# unodongdiendienap.net
KiCad netlist of a schematic drawn in Altium Designer
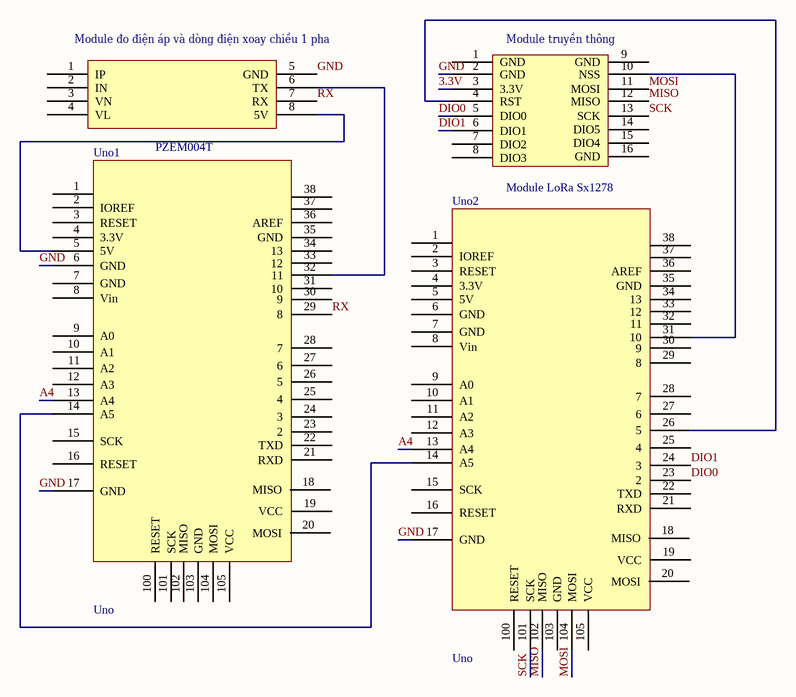
[diagram p0: unodongdiendienap.SchDoc]

(export (version "E")
  (design (tool "Eeschema 10.0.6"))
  (components
    (comp (ref "Module truyền thông")
      (value "Module LoRa Sx1278")
      (footprint "PCBLoRa")
      (libsource (lib "LoRa") (part "Component_1"))
    )
    (comp (ref "Module đo điện áp và dòng điện xoay chiều 1 pha")
      (value "PZEM004T")
      (libsource (lib "pzem") (part "PZEM004T"))
    )
    (comp (ref "Uno1") (value "Uno") (footprint "PCBComponent_1") (libsource (lib "uno") (part "Uno")))
    (comp (ref "Uno2") (value "Uno") (footprint "PCBComponent_1") (libsource (lib "uno") (part "Uno")))
  )
  (nets
    (net (code "1") (name "/3.3V") (class "Default")
      (node (ref "Module truyền thông") (pin "3") (pinfunction "3.3V_3") (pintype "passive"))
    )
    (net (code "2") (name "/A4") (class "Default")
      (node (ref "Uno1") (pin "13") (pinfunction "A4_13") (pintype "passive"))
      (node (ref "Uno2") (pin "13") (pinfunction "A4_13") (pintype "passive"))
    )
    (net (code "3") (name "/DIO0") (class "Default")
      (node (ref "Module truyền thông") (pin "5") (pinfunction "DIO0_5") (pintype "passive"))
      (node (ref "Uno2") (pin "23") (pinfunction "2_23") (pintype "passive"))
    )
    (net (code "4") (name "/DIO1") (class "Default")
      (node (ref "Module truyền thông") (pin "6") (pinfunction "DIO1_6") (pintype "passive"))
      (node (ref "Uno2") (pin "24") (pinfunction "3_24") (pintype "passive"))
    )
    (net (code "5") (name "/GND") (class "Default")
      (node (ref "Module truyền thông") (pin "2") (pinfunction "GND_2") (pintype "passive"))
      (node (ref "Module đo điện áp và dòng điện xoay chiều 1 pha") (pin "5") (pinfunction "GND_5") (pintype "passive"))
      (node (ref "Uno1") (pin "17") (pinfunction "GND_17") (pintype "passive"))
      (node (ref "Uno1") (pin "6") (pinfunction "GND_6") (pintype "passive"))
      (node (ref "Uno2") (pin "17") (pinfunction "GND_17") (pintype "passive"))
    )
    (net (code "6") (name "/MISO") (class "Default")
      (node (ref "Module truyền thông") (pin "12") (pinfunction "MISO_12") (pintype "passive"))
      (node (ref "Uno2") (pin "102") (pinfunction "MISO_102") (pintype "passive"))
    )
    (net (code "7") (name "/MOSI") (class "Default")
      (node (ref "Module truyền thông") (pin "11") (pinfunction "MOSI_11") (pintype "passive"))
      (node (ref "Uno2") (pin "104") (pinfunction "MOSI_104") (pintype "passive"))
    )
    (net (code "8") (name "/RX") (class "Default")
      (node (ref "Module đo điện áp và dòng điện xoay chiều 1 pha") (pin "7") (pinfunction "RX_7") (pintype "passive"))
      (node (ref "Uno1") (pin "29") (pinfunction "8_29") (pintype "passive"))
    )
    (net (code "9") (name "/SCK") (class "Default")
      (node (ref "Module truyền thông") (pin "13") (pinfunction "SCK_13") (pintype "passive"))
      (node (ref "Uno2") (pin "101") (pinfunction "SCK_101") (pintype "passive"))
    )
    (net (code "10") (name "Net-(Module truyền thông-NSS)") (class "Default")
      (node (ref "Module truyền thông") (pin "10") (pinfunction "NSS_10") (pintype "passive"))
      (node (ref "Uno2") (pin "31") (pinfunction "10_31") (pintype "passive"))
    )
    (net (code "11") (name "Net-(Module truyền thông-RST)") (class "Default")
      (node (ref "Module truyền thông") (pin "4") (pinfunction "RST_4") (pintype "passive"))
      (node (ref "Uno2") (pin "26") (pinfunction "5_26") (pintype "passive"))
    )
    (net (code "12") (name "Net-(Module đo điện áp và dòng điện xoay chiều 1 pha-5V)") (class "Default")
      (node (ref "Module đo điện áp và dòng điện xoay chiều 1 pha") (pin "8") (pinfunction "5V_8") (pintype "passive"))
      (node (ref "Uno1") (pin "5") (pinfunction "5V_5") (pintype "passive"))
    )
    (net (code "13") (name "Net-(Module đo điện áp và dòng điện xoay chiều 1 pha-TX)") (class "Default")
      (node (ref "Module đo điện áp và dòng điện xoay chiều 1 pha") (pin "6") (pinfunction "TX_6") (pintype "passive"))
      (node (ref "Uno1") (pin "32") (pinfunction "11_32") (pintype "passive"))
    )
    (net (code "14") (name "Net-(Uno1-A5)") (class "Default")
      (node (ref "Uno1") (pin "14") (pinfunction "A5_14") (pintype "passive"))
      (node (ref "Uno2") (pin "14") (pinfunction "A5_14") (pintype "passive"))
    )
    (net (code "15") (name "unconnected-(Module truyền thông-DIO2-Pad7)") (class "Default")
      (node (ref "Module truyền thông") (pin "7") (pinfunction "DIO2_7") (pintype "passive"))
    )
    (net (code "16") (name "unconnected-(Module truyền thông-DIO3-Pad8)") (class "Default")
      (node (ref "Module truyền thông") (pin "8") (pinfunction "DIO3_8") (pintype "passive"))
    )
    (net (code "17") (name "unconnected-(Module truyền thông-DIO4-Pad15)") (class "Default")
      (node (ref "Module truyền thông") (pin "15") (pinfunction "DIO4_15") (pintype "passive"))
    )
    (net (code "18") (name "unconnected-(Module truyền thông-DIO5-Pad14)") (class "Default")
      (node (ref "Module truyền thông") (pin "14") (pinfunction "DIO5_14") (pintype "passive"))
    )
    (net (code "19") (name "unconnected-(Module truyền thông-GND-Pad1)") (class "Default")
      (node (ref "Module truyền thông") (pin "1") (pinfunction "GND_1") (pintype "passive"))
    )
    (net (code "20") (name "unconnected-(Module truyền thông-GND-Pad9)") (class "Default")
      (node (ref "Module truyền thông") (pin "9") (pinfunction "GND_9") (pintype "passive"))
    )
    (net (code "21") (name "unconnected-(Module truyền thông-GND-Pad16)") (class "Default")
      (node (ref "Module truyền thông") (pin "16") (pinfunction "GND_16") (pintype "passive"))
    )
    (net (code "22") (name "unconnected-(Module đo điện áp và dòng điện xoay chiều 1 pha-IN-Pad2)") (class "Default")
      (node (ref "Module đo điện áp và dòng điện xoay chiều 1 pha") (pin "2") (pinfunction "IN_2") (pintype "passive"))
    )
    (net (code "23") (name "unconnected-(Module đo điện áp và dòng điện xoay chiều 1 pha-IP-Pad1)") (class "Default")
      (node (ref "Module đo điện áp và dòng điện xoay chiều 1 pha") (pin "1") (pinfunction "IP_1") (pintype "passive"))
    )
    (net (code "24") (name "unconnected-(Module đo điện áp và dòng điện xoay chiều 1 pha-VL-Pad4)") (class "Default")
      (node (ref "Module đo điện áp và dòng điện xoay chiều 1 pha") (pin "4") (pinfunction "VL_4") (pintype "passive"))
    )
    (net (code "25") (name "unconnected-(Module đo điện áp và dòng điện xoay chiều 1 pha-VN-Pad3)") (class "Default")
      (node (ref "Module đo điện áp và dòng điện xoay chiều 1 pha") (pin "3") (pinfunction "VN_3") (pintype "passive"))
    )
    (net (code "26") (name "unconnected-(Uno1-2-Pad23)") (class "Default")
      (node (ref "Uno1") (pin "23") (pinfunction "2_23") (pintype "passive"))
    )
    (net (code "27") (name "unconnected-(Uno1-3-Pad24)") (class "Default")
      (node (ref "Uno1") (pin "24") (pinfunction "3_24") (pintype "passive"))
    )
    (net (code "28") (name "unconnected-(Uno1-3.3V-Pad4)") (class "Default")
      (node (ref "Uno1") (pin "4") (pinfunction "3.3V_4") (pintype "passive"))
    )
    (net (code "29") (name "unconnected-(Uno1-4-Pad25)") (class "Default")
      (node (ref "Uno1") (pin "25") (pinfunction "4_25") (pintype "passive"))
    )
    (net (code "30") (name "unconnected-(Uno1-5-Pad26)") (class "Default")
      (node (ref "Uno1") (pin "26") (pinfunction "5_26") (pintype "passive"))
    )
    (net (code "31") (name "unconnected-(Uno1-6-Pad27)") (class "Default")
      (node (ref "Uno1") (pin "27") (pinfunction "6_27") (pintype "passive"))
    )
    (net (code "32") (name "unconnected-(Uno1-7-Pad28)") (class "Default")
      (node (ref "Uno1") (pin "28") (pinfunction "7_28") (pintype "passive"))
    )
    (net (code "33") (name "unconnected-(Uno1-9-Pad30)") (class "Default")
      (node (ref "Uno1") (pin "30") (pinfunction "9_30") (pintype "passive"))
    )
    (net (code "34") (name "unconnected-(Uno1-10-Pad31)") (class "Default")
      (node (ref "Uno1") (pin "31") (pinfunction "10_31") (pintype "passive"))
    )
    (net (code "35") (name "unconnected-(Uno1-12-Pad33)") (class "Default")
      (node (ref "Uno1") (pin "33") (pinfunction "12_33") (pintype "passive"))
    )
    (net (code "36") (name "unconnected-(Uno1-13-Pad34)") (class "Default")
      (node (ref "Uno1") (pin "34") (pinfunction "13_34") (pintype "passive"))
    )
    (net (code "37") (name "unconnected-(Uno1-A0-Pad9)") (class "Default")
      (node (ref "Uno1") (pin "9") (pinfunction "A0_9") (pintype "passive"))
    )
    (net (code "38") (name "unconnected-(Uno1-A1-Pad10)") (class "Default")
      (node (ref "Uno1") (pin "10") (pinfunction "A1_10") (pintype "passive"))
    )
    (net (code "39") (name "unconnected-(Uno1-A2-Pad11)") (class "Default")
      (node (ref "Uno1") (pin "11") (pinfunction "A2_11") (pintype "passive"))
    )
    (net (code "40") (name "unconnected-(Uno1-A3-Pad12)") (class "Default")
      (node (ref "Uno1") (pin "12") (pinfunction "A3_12") (pintype "passive"))
    )
    (net (code "41") (name "unconnected-(Uno1-AREF-Pad36)") (class "Default")
      (node (ref "Uno1") (pin "36") (pinfunction "AREF_36") (pintype "passive"))
    )
    (net (code "42") (name "unconnected-(Uno1-GND-Pad7)") (class "Default")
      (node (ref "Uno1") (pin "7") (pinfunction "GND_7") (pintype "passive"))
    )
    (net (code "43") (name "unconnected-(Uno1-GND-Pad35)") (class "Default")
      (node (ref "Uno1") (pin "35") (pinfunction "GND_35") (pintype "passive"))
    )
    (net (code "44") (name "unconnected-(Uno1-GND-Pad103)") (class "Default")
      (node (ref "Uno1") (pin "103") (pinfunction "GND_103") (pintype "passive"))
    )
    (net (code "45") (name "unconnected-(Uno1-IOREF-Pad2)") (class "Default")
      (node (ref "Uno1") (pin "2") (pinfunction "IOREF_2") (pintype "passive"))
    )
    (net (code "46") (name "unconnected-(Uno1-MISO-Pad18)") (class "Default")
      (node (ref "Uno1") (pin "18") (pinfunction "MISO_18") (pintype "passive"))
    )
    (net (code "47") (name "unconnected-(Uno1-MISO-Pad102)") (class "Default")
      (node (ref "Uno1") (pin "102") (pinfunction "MISO_102") (pintype "passive"))
    )
    (net (code "48") (name "unconnected-(Uno1-MOSI-Pad20)") (class "Default")
      (node (ref "Uno1") (pin "20") (pinfunction "MOSI_20") (pintype "passive"))
    )
    (net (code "49") (name "unconnected-(Uno1-MOSI-Pad104)") (class "Default")
      (node (ref "Uno1") (pin "104") (pinfunction "MOSI_104") (pintype "passive"))
    )
    (net (code "50") (name "unconnected-(Uno1-Pad1)") (class "Default")
      (node (ref "Uno1") (pin "1") (pintype "passive"))
    )
    (net (code "51") (name "unconnected-(Uno1-Pad37)") (class "Default")
      (node (ref "Uno1") (pin "37") (pintype "passive"))
    )
    (net (code "52") (name "unconnected-(Uno1-Pad38)") (class "Default")
      (node (ref "Uno1") (pin "38") (pintype "passive"))
    )
    (net (code "53") (name "unconnected-(Uno1-RESET-Pad3)") (class "Default")
      (node (ref "Uno1") (pin "3") (pinfunction "RESET_3") (pintype "passive"))
    )
    (net (code "54") (name "unconnected-(Uno1-RESET-Pad16)") (class "Default")
      (node (ref "Uno1") (pin "16") (pinfunction "RESET_16") (pintype "passive"))
    )
    (net (code "55") (name "unconnected-(Uno1-RESET-Pad100)") (class "Default")
      (node (ref "Uno1") (pin "100") (pinfunction "RESET_100") (pintype "passive"))
    )
    (net (code "56") (name "unconnected-(Uno1-RXD-Pad21)") (class "Default")
      (node (ref "Uno1") (pin "21") (pinfunction "RXD_21") (pintype "passive"))
    )
    (net (code "57") (name "unconnected-(Uno1-SCK-Pad15)") (class "Default")
      (node (ref "Uno1") (pin "15") (pinfunction "SCK_15") (pintype "passive"))
    )
    (net (code "58") (name "unconnected-(Uno1-SCK-Pad101)") (class "Default")
      (node (ref "Uno1") (pin "101") (pinfunction "SCK_101") (pintype "passive"))
    )
    (net (code "59") (name "unconnected-(Uno1-TXD-Pad22)") (class "Default")
      (node (ref "Uno1") (pin "22") (pinfunction "TXD_22") (pintype "passive"))
    )
    (net (code "60") (name "unconnected-(Uno1-VCC-Pad19)") (class "Default")
      (node (ref "Uno1") (pin "19") (pinfunction "VCC_19") (pintype "passive"))
    )
    (net (code "61") (name "unconnected-(Uno1-VCC-Pad105)") (class "Default")
      (node (ref "Uno1") (pin "105") (pinfunction "VCC_105") (pintype "passive"))
    )
    (net (code "62") (name "unconnected-(Uno1-Vin-Pad8)") (class "Default")
      (node (ref "Uno1") (pin "8") (pinfunction "Vin_8") (pintype "passive"))
    )
    (net (code "63") (name "unconnected-(Uno2-3.3V-Pad4)") (class "Default")
      (node (ref "Uno2") (pin "4") (pinfunction "3.3V_4") (pintype "passive"))
    )
    (net (code "64") (name "unconnected-(Uno2-4-Pad25)") (class "Default")
      (node (ref "Uno2") (pin "25") (pinfunction "4_25") (pintype "passive"))
    )
    (net (code "65") (name "unconnected-(Uno2-5V-Pad5)") (class "Default")
      (node (ref "Uno2") (pin "5") (pinfunction "5V_5") (pintype "passive"))
    )
    (net (code "66") (name "unconnected-(Uno2-6-Pad27)") (class "Default")
      (node (ref "Uno2") (pin "27") (pinfunction "6_27") (pintype "passive"))
    )
    (net (code "67") (name "unconnected-(Uno2-7-Pad28)") (class "Default")
      (node (ref "Uno2") (pin "28") (pinfunction "7_28") (pintype "passive"))
    )
    (net (code "68") (name "unconnected-(Uno2-8-Pad29)") (class "Default")
      (node (ref "Uno2") (pin "29") (pinfunction "8_29") (pintype "passive"))
    )
    (net (code "69") (name "unconnected-(Uno2-9-Pad30)") (class "Default")
      (node (ref "Uno2") (pin "30") (pinfunction "9_30") (pintype "passive"))
    )
    (net (code "70") (name "unconnected-(Uno2-11-Pad32)") (class "Default")
      (node (ref "Uno2") (pin "32") (pinfunction "11_32") (pintype "passive"))
    )
    (net (code "71") (name "unconnected-(Uno2-12-Pad33)") (class "Default")
      (node (ref "Uno2") (pin "33") (pinfunction "12_33") (pintype "passive"))
    )
    (net (code "72") (name "unconnected-(Uno2-13-Pad34)") (class "Default")
      (node (ref "Uno2") (pin "34") (pinfunction "13_34") (pintype "passive"))
    )
    (net (code "73") (name "unconnected-(Uno2-A0-Pad9)") (class "Default")
      (node (ref "Uno2") (pin "9") (pinfunction "A0_9") (pintype "passive"))
    )
    (net (code "74") (name "unconnected-(Uno2-A1-Pad10)") (class "Default")
      (node (ref "Uno2") (pin "10") (pinfunction "A1_10") (pintype "passive"))
    )
    (net (code "75") (name "unconnected-(Uno2-A2-Pad11)") (class "Default")
      (node (ref "Uno2") (pin "11") (pinfunction "A2_11") (pintype "passive"))
    )
    (net (code "76") (name "unconnected-(Uno2-A3-Pad12)") (class "Default")
      (node (ref "Uno2") (pin "12") (pinfunction "A3_12") (pintype "passive"))
    )
    (net (code "77") (name "unconnected-(Uno2-AREF-Pad36)") (class "Default")
      (node (ref "Uno2") (pin "36") (pinfunction "AREF_36") (pintype "passive"))
    )
    (net (code "78") (name "unconnected-(Uno2-GND-Pad6)") (class "Default")
      (node (ref "Uno2") (pin "6") (pinfunction "GND_6") (pintype "passive"))
    )
    (net (code "79") (name "unconnected-(Uno2-GND-Pad7)") (class "Default")
      (node (ref "Uno2") (pin "7") (pinfunction "GND_7") (pintype "passive"))
    )
    (net (code "80") (name "unconnected-(Uno2-GND-Pad35)") (class "Default")
      (node (ref "Uno2") (pin "35") (pinfunction "GND_35") (pintype "passive"))
    )
    (net (code "81") (name "unconnected-(Uno2-GND-Pad103)") (class "Default")
      (node (ref "Uno2") (pin "103") (pinfunction "GND_103") (pintype "passive"))
    )
    (net (code "82") (name "unconnected-(Uno2-IOREF-Pad2)") (class "Default")
      (node (ref "Uno2") (pin "2") (pinfunction "IOREF_2") (pintype "passive"))
    )
    (net (code "83") (name "unconnected-(Uno2-MISO-Pad18)") (class "Default")
      (node (ref "Uno2") (pin "18") (pinfunction "MISO_18") (pintype "passive"))
    )
    (net (code "84") (name "unconnected-(Uno2-MOSI-Pad20)") (class "Default")
      (node (ref "Uno2") (pin "20") (pinfunction "MOSI_20") (pintype "passive"))
    )
    (net (code "85") (name "unconnected-(Uno2-Pad1)") (class "Default")
      (node (ref "Uno2") (pin "1") (pintype "passive"))
    )
    (net (code "86") (name "unconnected-(Uno2-Pad37)") (class "Default")
      (node (ref "Uno2") (pin "37") (pintype "passive"))
    )
    (net (code "87") (name "unconnected-(Uno2-Pad38)") (class "Default")
      (node (ref "Uno2") (pin "38") (pintype "passive"))
    )
    (net (code "88") (name "unconnected-(Uno2-RESET-Pad3)") (class "Default")
      (node (ref "Uno2") (pin "3") (pinfunction "RESET_3") (pintype "passive"))
    )
    (net (code "89") (name "unconnected-(Uno2-RESET-Pad16)") (class "Default")
      (node (ref "Uno2") (pin "16") (pinfunction "RESET_16") (pintype "passive"))
    )
    (net (code "90") (name "unconnected-(Uno2-RESET-Pad100)") (class "Default")
      (node (ref "Uno2") (pin "100") (pinfunction "RESET_100") (pintype "passive"))
    )
    (net (code "91") (name "unconnected-(Uno2-RXD-Pad21)") (class "Default")
      (node (ref "Uno2") (pin "21") (pinfunction "RXD_21") (pintype "passive"))
    )
    (net (code "92") (name "unconnected-(Uno2-SCK-Pad15)") (class "Default")
      (node (ref "Uno2") (pin "15") (pinfunction "SCK_15") (pintype "passive"))
    )
    (net (code "93") (name "unconnected-(Uno2-TXD-Pad22)") (class "Default")
      (node (ref "Uno2") (pin "22") (pinfunction "TXD_22") (pintype "passive"))
    )
    (net (code "94") (name "unconnected-(Uno2-VCC-Pad19)") (class "Default")
      (node (ref "Uno2") (pin "19") (pinfunction "VCC_19") (pintype "passive"))
    )
    (net (code "95") (name "unconnected-(Uno2-VCC-Pad105)") (class "Default")
      (node (ref "Uno2") (pin "105") (pinfunction "VCC_105") (pintype "passive"))
    )
    (net (code "96") (name "unconnected-(Uno2-Vin-Pad8)") (class "Default")
      (node (ref "Uno2") (pin "8") (pinfunction "Vin_8") (pintype "passive"))
    )
  )
)
